# Main.net
KiCad netlist of a schematic drawn in Altium Designer
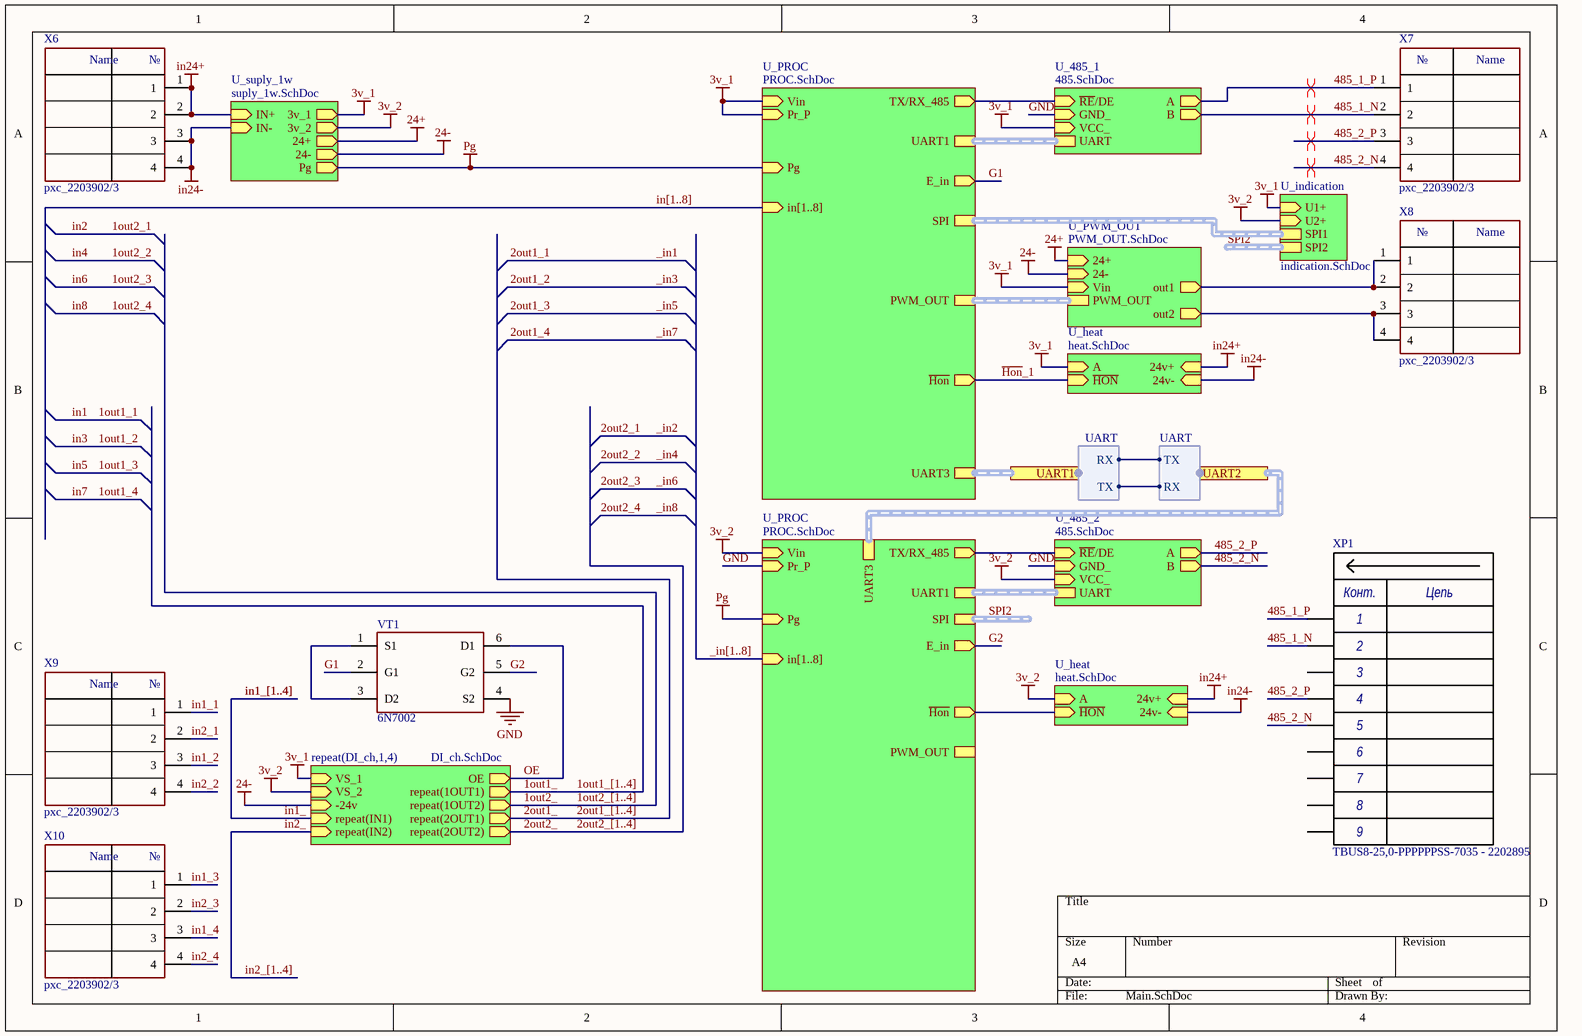
[diagram p0: Main.SchDoc]

(export (version "E")
  (design (tool "Eeschema 10.0.6"))
  (components
    (comp (ref "VT1") (value "6N7002") (footprint "sot-23-6") (libsource (lib "lib") (part "6n7002")))
    (comp (ref "X6")
      (value "pxc_2203902/3")
      (footprint "pxc_2203902")
      (libsource (lib "lib") (part "pxc_2203902/3"))
    )
    (comp (ref "X7")
      (value "pxc_2203902/3")
      (footprint "pxc_2203902")
      (libsource (lib "") (part "pxc_2203902/3_1"))
    )
    (comp (ref "X8")
      (value "pxc_2203902/3")
      (footprint "pxc_2203903")
      (libsource (lib "") (part "pxc_2203902/3_1"))
    )
    (comp (ref "X9")
      (value "pxc_2203902/3")
      (footprint "pxc_2203903")
      (libsource (lib "lib") (part "pxc_2203902/3"))
    )
    (comp (ref "X10")
      (value "pxc_2203902/3")
      (footprint "pxc_2203903")
      (libsource (lib "lib") (part "pxc_2203902/3"))
    )
    (comp (ref "XP1")
      (value "TBUS8-25,0-PPPPPPSS-7035 - 2202895")
      (footprint "TBUS8-25,0-PPPPPPSS-7035 - 2202895")
      (libsource (lib "lib") (part "TBUS8-25,0-PPPPPPSS-7035 - 2202895"))
    )
  )
  (nets
    (net (code "19") (name "/485_1_N") (class "Default")
      (node (ref "X7") (pin "2") (pinfunction "2_2") (pintype "passive"))
      (node (ref "XP1") (pin "2") (pinfunction "2c_2") (pintype "passive"))
    )
    (net (code "20") (name "/485_1_P") (class "Default")
      (node (ref "X7") (pin "1") (pinfunction "1_1") (pintype "passive"))
      (node (ref "XP1") (pin "1") (pinfunction "1c_1") (pintype "passive"))
    )
    (net (code "21") (name "/485_2_N") (class "Default")
      (node (ref "X7") (pin "4") (pinfunction "4_4") (pintype "passive"))
      (node (ref "XP1") (pin "5") (pinfunction "5c_5") (pintype "passive"))
    )
    (net (code "22") (name "/485_2_P") (class "Default")
      (node (ref "X7") (pin "3") (pinfunction "3_3") (pintype "passive"))
      (node (ref "XP1") (pin "4") (pinfunction "4c_4") (pintype "passive"))
    )
    (net (code "23") (name "/G1") (class "Default")
      (node (ref "VT1") (pin "2") (pinfunction "G1_2") (pintype "passive"))
    )
    (net (code "24") (name "/G2") (class "Default")
      (node (ref "VT1") (pin "5") (pinfunction "G2_5") (pintype "passive"))
    )
    (net (code "25") (name "/OE") (class "Default")
      (node (ref "VT1") (pin "6") (pinfunction "D1_6") (pintype "passive"))
    )
    (net (code "42") (name "/in1_1") (class "Default")
      (node (ref "X9") (pin "1") (pinfunction "1_1") (pintype "passive"))
    )
    (net (code "43") (name "/in1_2") (class "Default")
      (node (ref "X9") (pin "3") (pinfunction "3_3") (pintype "passive"))
    )
    (net (code "44") (name "/in1_3") (class "Default")
      (node (ref "X10") (pin "1") (pinfunction "1_1") (pintype "passive"))
    )
    (net (code "45") (name "/in1_4") (class "Default")
      (node (ref "X10") (pin "3") (pinfunction "3_3") (pintype "passive"))
    )
    (net (code "48") (name "/in2_1") (class "Default")
      (node (ref "X9") (pin "2") (pinfunction "2_2") (pintype "passive"))
    )
    (net (code "49") (name "/in2_2") (class "Default")
      (node (ref "X9") (pin "4") (pinfunction "4_4") (pintype "passive"))
    )
    (net (code "50") (name "/in2_3") (class "Default")
      (node (ref "X10") (pin "2") (pinfunction "2_2") (pintype "passive"))
    )
    (net (code "51") (name "/in2_4") (class "Default")
      (node (ref "X10") (pin "4") (pinfunction "4_4") (pintype "passive"))
    )
    (net (code "54") (name "/out1") (class "Default")
      (node (ref "X8") (pin "1") (pinfunction "1_1") (pintype "passive"))
      (node (ref "X8") (pin "2") (pinfunction "2_2") (pintype "passive"))
    )
    (net (code "55") (name "/out2") (class "Default")
      (node (ref "X8") (pin "3") (pinfunction "3_3") (pintype "passive"))
      (node (ref "X8") (pin "4") (pinfunction "4_4") (pintype "passive"))
    )
    (net (code "64") (name "GND") (class "Default")
      (node (ref "VT1") (pin "4") (pinfunction "S2_4") (pintype "passive"))
    )
    (net (code "65") (name "Net-(VT1-D2)") (class "Default")
      (node (ref "VT1") (pin "1") (pinfunction "S1_1") (pintype "passive"))
      (node (ref "VT1") (pin "3") (pinfunction "D2_3") (pintype "passive"))
    )
    (net (code "67") (name "in24+") (class "Default")
      (node (ref "X6") (pin "1") (pinfunction "1_1") (pintype "passive"))
      (node (ref "X6") (pin "2") (pinfunction "2_2") (pintype "passive"))
    )
    (net (code "68") (name "in24-") (class "Default")
      (node (ref "X6") (pin "3") (pinfunction "3_3") (pintype "passive"))
      (node (ref "X6") (pin "4") (pinfunction "4_4") (pintype "passive"))
    )
    (net (code "69") (name "unconnected-(XP1-3c-Pad3)") (class "Default")
      (node (ref "XP1") (pin "3") (pinfunction "3c_3") (pintype "passive"))
    )
    (net (code "70") (name "unconnected-(XP1-6c-Pad6)") (class "Default")
      (node (ref "XP1") (pin "6") (pinfunction "6c_6") (pintype "passive"))
    )
    (net (code "71") (name "unconnected-(XP1-7e-Pad7)") (class "Default")
      (node (ref "XP1") (pin "7") (pinfunction "7e_7") (pintype "passive"))
    )
    (net (code "72") (name "unconnected-(XP1-8e-Pad8)") (class "Default")
      (node (ref "XP1") (pin "8") (pinfunction "8e_8") (pintype "passive"))
    )
    (net (code "73") (name "unconnected-(XP1-Pad9)") (class "Default")
      (node (ref "XP1") (pin "9") (pinfunction "9_9") (pintype "passive"))
    )
  )
)
